# AccessPanelV1.net
KiCad netlist of a schematic drawn in EAGLE
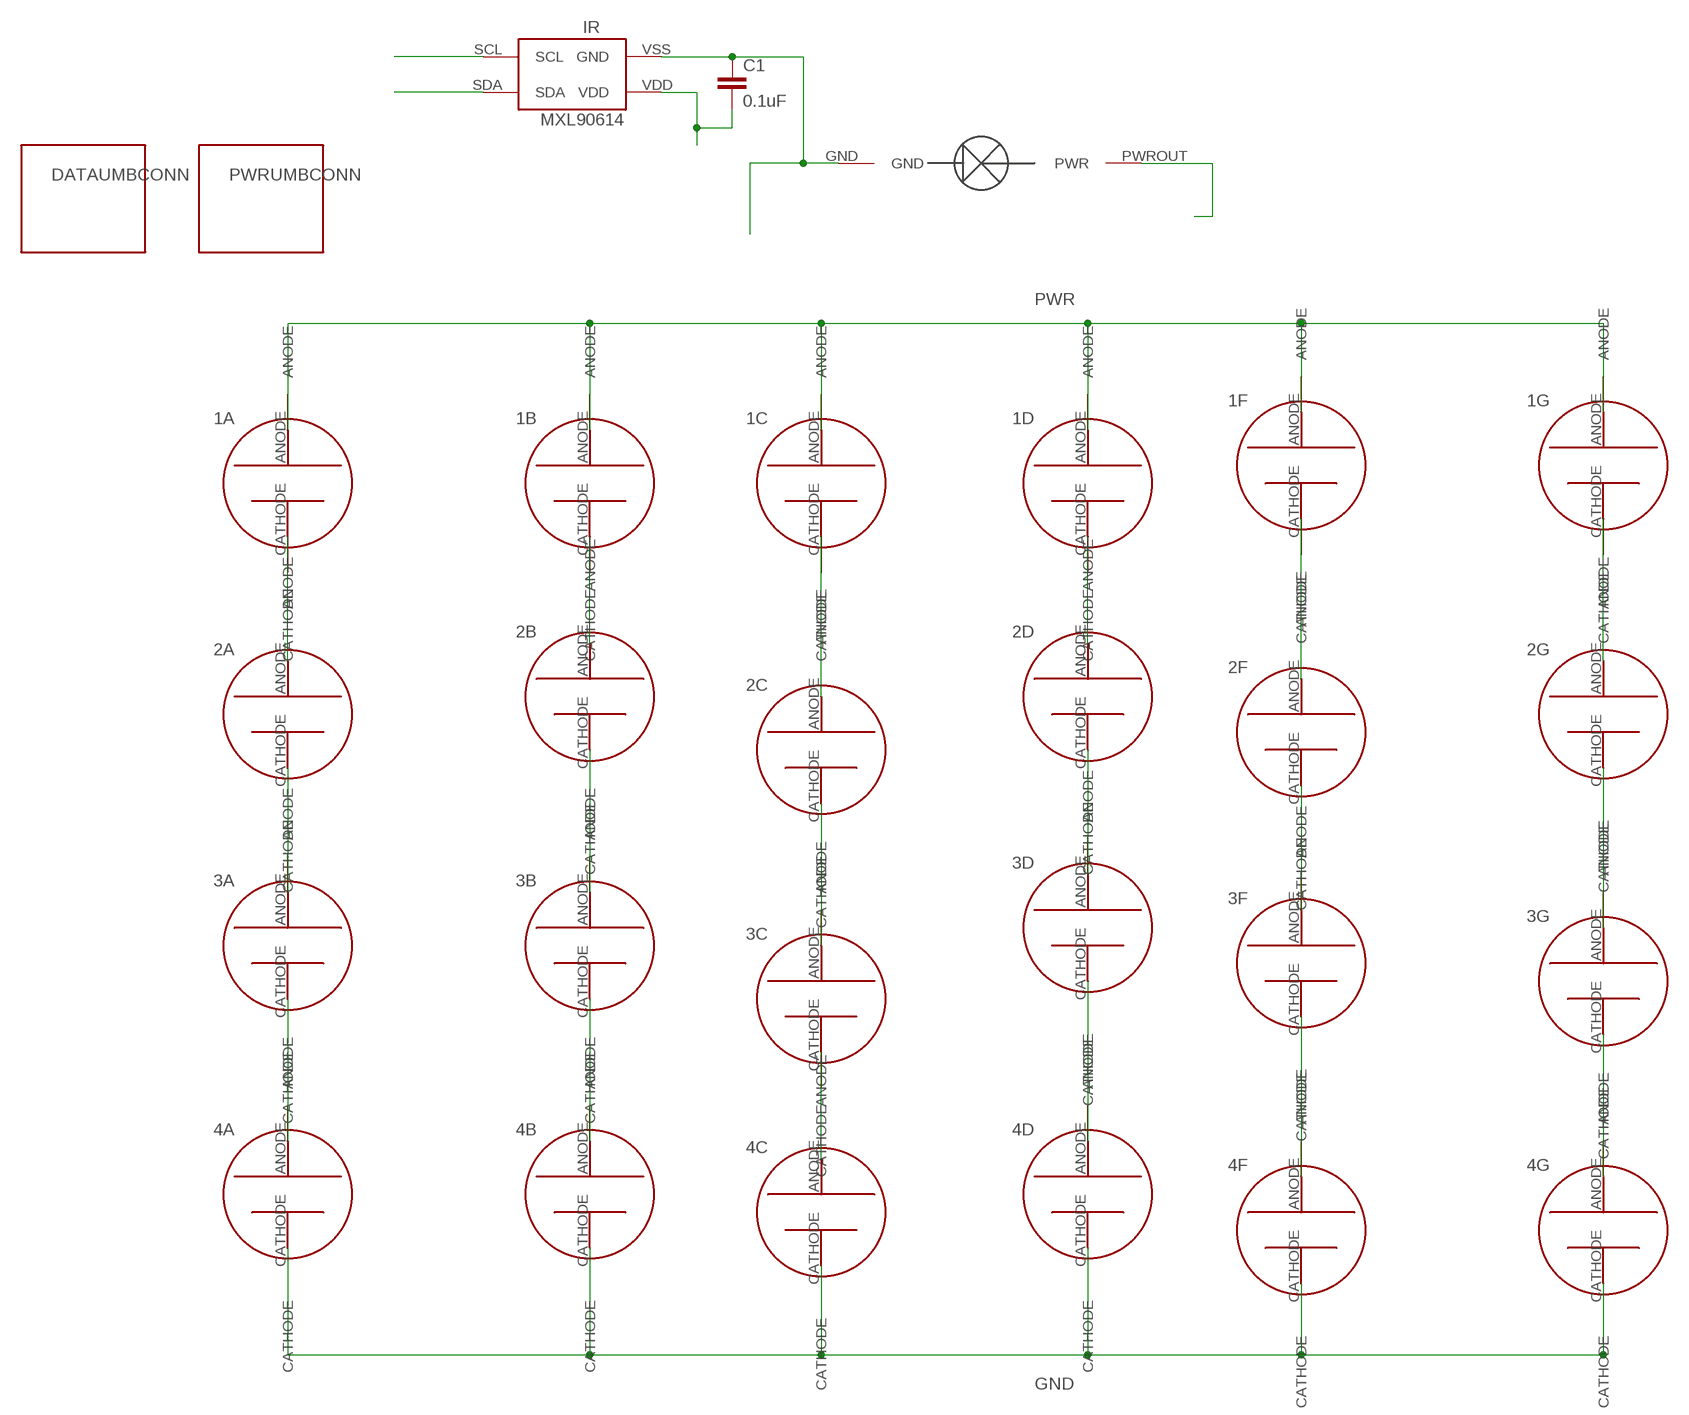
[diagram p0: schematic, sheet 1]

(export (version "E")
  (design (tool "Eeschema 10.0.6"))
  (components
    (comp (ref "1A")
      (value "NEWSOLARPANEL")
      (footprint "eagle-import:SOLARCELL2")
      (libsource (lib "eagle-import") (part "NEWSOLARPANEL"))
    )
    (comp (ref "1B")
      (value "NEWSOLARPANEL")
      (footprint "eagle-import:SOLARCELL2")
      (libsource (lib "eagle-import") (part "NEWSOLARPANEL"))
    )
    (comp (ref "1C")
      (value "NEWSOLARPANEL")
      (footprint "eagle-import:SOLARCELL2")
      (libsource (lib "eagle-import") (part "NEWSOLARPANEL"))
    )
    (comp (ref "1D")
      (value "NEWSOLARPANEL")
      (footprint "eagle-import:SOLARCELL2")
      (libsource (lib "eagle-import") (part "NEWSOLARPANEL"))
    )
    (comp (ref "1F")
      (value "NEWSOLARPANEL")
      (footprint "eagle-import:SOLARCELL2")
      (libsource (lib "eagle-import") (part "NEWSOLARPANEL"))
    )
    (comp (ref "1G")
      (value "NEWSOLARPANEL")
      (footprint "eagle-import:SOLARCELL2")
      (libsource (lib "eagle-import") (part "NEWSOLARPANEL"))
    )
    (comp (ref "2A")
      (value "NEWSOLARPANEL")
      (footprint "eagle-import:SOLARCELL2")
      (libsource (lib "eagle-import") (part "NEWSOLARPANEL"))
    )
    (comp (ref "2B")
      (value "NEWSOLARPANEL")
      (footprint "eagle-import:SOLARCELL2")
      (libsource (lib "eagle-import") (part "NEWSOLARPANEL"))
    )
    (comp (ref "2C")
      (value "NEWSOLARPANEL")
      (footprint "eagle-import:SOLARCELL2")
      (libsource (lib "eagle-import") (part "NEWSOLARPANEL"))
    )
    (comp (ref "2D")
      (value "NEWSOLARPANEL")
      (footprint "eagle-import:SOLARCELL2")
      (libsource (lib "eagle-import") (part "NEWSOLARPANEL"))
    )
    (comp (ref "2F")
      (value "NEWSOLARPANEL")
      (footprint "eagle-import:SOLARCELL2")
      (libsource (lib "eagle-import") (part "NEWSOLARPANEL"))
    )
    (comp (ref "2G")
      (value "NEWSOLARPANEL")
      (footprint "eagle-import:SOLARCELL2")
      (libsource (lib "eagle-import") (part "NEWSOLARPANEL"))
    )
    (comp (ref "3A")
      (value "NEWSOLARPANEL")
      (footprint "eagle-import:SOLARCELL2")
      (libsource (lib "eagle-import") (part "NEWSOLARPANEL"))
    )
    (comp (ref "3B")
      (value "NEWSOLARPANEL")
      (footprint "eagle-import:SOLARCELL2")
      (libsource (lib "eagle-import") (part "NEWSOLARPANEL"))
    )
    (comp (ref "3C")
      (value "NEWSOLARPANEL")
      (footprint "eagle-import:SOLARCELL2")
      (libsource (lib "eagle-import") (part "NEWSOLARPANEL"))
    )
    (comp (ref "3D")
      (value "NEWSOLARPANEL")
      (footprint "eagle-import:SOLARCELL2")
      (libsource (lib "eagle-import") (part "NEWSOLARPANEL"))
    )
    (comp (ref "3F")
      (value "NEWSOLARPANEL")
      (footprint "eagle-import:SOLARCELL2")
      (libsource (lib "eagle-import") (part "NEWSOLARPANEL"))
    )
    (comp (ref "3G")
      (value "NEWSOLARPANEL")
      (footprint "eagle-import:SOLARCELL2")
      (libsource (lib "eagle-import") (part "NEWSOLARPANEL"))
    )
    (comp (ref "4A")
      (value "NEWSOLARPANEL")
      (footprint "eagle-import:SOLARCELL2")
      (libsource (lib "eagle-import") (part "NEWSOLARPANEL"))
    )
    (comp (ref "4B")
      (value "NEWSOLARPANEL")
      (footprint "eagle-import:SOLARCELL2")
      (libsource (lib "eagle-import") (part "NEWSOLARPANEL"))
    )
    (comp (ref "4C")
      (value "NEWSOLARPANEL")
      (footprint "eagle-import:SOLARCELL2")
      (libsource (lib "eagle-import") (part "NEWSOLARPANEL"))
    )
    (comp (ref "4D")
      (value "NEWSOLARPANEL")
      (footprint "eagle-import:SOLARCELL2")
      (libsource (lib "eagle-import") (part "NEWSOLARPANEL"))
    )
    (comp (ref "4F")
      (value "NEWSOLARPANEL")
      (footprint "eagle-import:SOLARCELL2")
      (libsource (lib "eagle-import") (part "NEWSOLARPANEL"))
    )
    (comp (ref "4G")
      (value "NEWSOLARPANEL")
      (footprint "eagle-import:SOLARCELL2")
      (libsource (lib "eagle-import") (part "NEWSOLARPANEL"))
    )
    (comp (ref "C1")
      (value "0.1uF")
      (footprint "eagle-import:0805")
      (libsource (lib "eagle-import") (part "CAP0805"))
    )
    (comp (ref "DATAUMBCONN")
      (value "HARWIN_PWR_BOARDMOUNT")
      (footprint "eagle-import:HARWIN_PWR_BOARDMOUNT")
      (libsource (lib "eagle-import") (part "HARWIN_PWR_BOARDMOUNT"))
    )
    (comp (ref "IR")
      (value "MXL90620")
      (footprint "eagle-import:MXL90614")
      (libsource (lib "eagle-import") (part "MXL90620"))
    )
    (comp (ref "PHD")
      (value "PHOTODETECTOR")
      (footprint "eagle-import:PHOTODECTORDEVICE2")
      (libsource (lib "eagle-import") (part "PHOTODETECTOR"))
    )
    (comp (ref "PWRUMBCONN")
      (value "HARWIN_PWR_BOARDMOUNT")
      (footprint "eagle-import:HARWIN_PWR_BOARDMOUNT")
      (libsource (lib "eagle-import") (part "HARWIN_PWR_BOARDMOUNT"))
    )
  )
  (nets
    (net (code "1") (name "/GND") (class "Default")
      (node (ref "4A") (pin "CATHODE") (pinfunction "CATHODE_CATHODE") (pintype "bidirectional"))
      (node (ref "4B") (pin "CATHODE") (pinfunction "CATHODE_CATHODE") (pintype "bidirectional"))
      (node (ref "4C") (pin "CATHODE") (pinfunction "CATHODE_CATHODE") (pintype "bidirectional"))
      (node (ref "4D") (pin "CATHODE") (pinfunction "CATHODE_CATHODE") (pintype "bidirectional"))
      (node (ref "4F") (pin "CATHODE") (pinfunction "CATHODE_CATHODE") (pintype "bidirectional"))
      (node (ref "4G") (pin "CATHODE") (pinfunction "CATHODE_CATHODE") (pintype "bidirectional"))
      (node (ref "C1") (pin "1") (pinfunction "1_1") (pintype "passive"))
      (node (ref "IR") (pin "VSS") (pinfunction "GND_VSS") (pintype "bidirectional"))
      (node (ref "PHD") (pin "GND") (pinfunction "GND_GND") (pintype "bidirectional"))
    )
    (net (code "2") (name "/PWR") (class "Default")
      (node (ref "1A") (pin "ANODE") (pinfunction "ANODE_ANODE") (pintype "bidirectional"))
      (node (ref "1B") (pin "ANODE") (pinfunction "ANODE_ANODE") (pintype "bidirectional"))
      (node (ref "1C") (pin "ANODE") (pinfunction "ANODE_ANODE") (pintype "bidirectional"))
      (node (ref "1D") (pin "ANODE") (pinfunction "ANODE_ANODE") (pintype "bidirectional"))
      (node (ref "1F") (pin "ANODE") (pinfunction "ANODE_ANODE") (pintype "bidirectional"))
      (node (ref "1G") (pin "ANODE") (pinfunction "ANODE_ANODE") (pintype "bidirectional"))
    )
    (net (code "3") (name "Net-(1A-PadCATHODE)") (class "Default")
      (node (ref "1A") (pin "CATHODE") (pinfunction "CATHODE_CATHODE") (pintype "bidirectional"))
      (node (ref "2A") (pin "ANODE") (pinfunction "ANODE_ANODE") (pintype "bidirectional"))
    )
    (net (code "4") (name "Net-(1B-PadCATHODE)") (class "Default")
      (node (ref "1B") (pin "CATHODE") (pinfunction "CATHODE_CATHODE") (pintype "bidirectional"))
      (node (ref "2B") (pin "ANODE") (pinfunction "ANODE_ANODE") (pintype "bidirectional"))
    )
    (net (code "5") (name "Net-(1C-PadCATHODE)") (class "Default")
      (node (ref "1C") (pin "CATHODE") (pinfunction "CATHODE_CATHODE") (pintype "bidirectional"))
      (node (ref "2C") (pin "ANODE") (pinfunction "ANODE_ANODE") (pintype "bidirectional"))
    )
    (net (code "6") (name "Net-(1D-PadCATHODE)") (class "Default")
      (node (ref "1D") (pin "CATHODE") (pinfunction "CATHODE_CATHODE") (pintype "bidirectional"))
      (node (ref "2D") (pin "ANODE") (pinfunction "ANODE_ANODE") (pintype "bidirectional"))
    )
    (net (code "7") (name "Net-(1F-PadCATHODE)") (class "Default")
      (node (ref "1F") (pin "CATHODE") (pinfunction "CATHODE_CATHODE") (pintype "bidirectional"))
      (node (ref "2F") (pin "ANODE") (pinfunction "ANODE_ANODE") (pintype "bidirectional"))
    )
    (net (code "8") (name "Net-(1G-PadCATHODE)") (class "Default")
      (node (ref "1G") (pin "CATHODE") (pinfunction "CATHODE_CATHODE") (pintype "bidirectional"))
      (node (ref "2G") (pin "ANODE") (pinfunction "ANODE_ANODE") (pintype "bidirectional"))
    )
    (net (code "9") (name "Net-(2A-PadCATHODE)") (class "Default")
      (node (ref "2A") (pin "CATHODE") (pinfunction "CATHODE_CATHODE") (pintype "bidirectional"))
      (node (ref "3A") (pin "ANODE") (pinfunction "ANODE_ANODE") (pintype "bidirectional"))
    )
    (net (code "10") (name "Net-(2B-PadCATHODE)") (class "Default")
      (node (ref "2B") (pin "CATHODE") (pinfunction "CATHODE_CATHODE") (pintype "bidirectional"))
      (node (ref "3B") (pin "ANODE") (pinfunction "ANODE_ANODE") (pintype "bidirectional"))
    )
    (net (code "11") (name "Net-(2C-PadCATHODE)") (class "Default")
      (node (ref "2C") (pin "CATHODE") (pinfunction "CATHODE_CATHODE") (pintype "bidirectional"))
      (node (ref "3C") (pin "ANODE") (pinfunction "ANODE_ANODE") (pintype "bidirectional"))
    )
    (net (code "12") (name "Net-(2D-PadCATHODE)") (class "Default")
      (node (ref "2D") (pin "CATHODE") (pinfunction "CATHODE_CATHODE") (pintype "bidirectional"))
      (node (ref "3D") (pin "ANODE") (pinfunction "ANODE_ANODE") (pintype "bidirectional"))
    )
    (net (code "13") (name "Net-(2F-PadCATHODE)") (class "Default")
      (node (ref "2F") (pin "CATHODE") (pinfunction "CATHODE_CATHODE") (pintype "bidirectional"))
      (node (ref "3F") (pin "ANODE") (pinfunction "ANODE_ANODE") (pintype "bidirectional"))
    )
    (net (code "14") (name "Net-(2G-PadCATHODE)") (class "Default")
      (node (ref "2G") (pin "CATHODE") (pinfunction "CATHODE_CATHODE") (pintype "bidirectional"))
      (node (ref "3G") (pin "ANODE") (pinfunction "ANODE_ANODE") (pintype "bidirectional"))
    )
    (net (code "15") (name "Net-(3A-PadCATHODE)") (class "Default")
      (node (ref "3A") (pin "CATHODE") (pinfunction "CATHODE_CATHODE") (pintype "bidirectional"))
      (node (ref "4A") (pin "ANODE") (pinfunction "ANODE_ANODE") (pintype "bidirectional"))
    )
    (net (code "16") (name "Net-(3B-PadCATHODE)") (class "Default")
      (node (ref "3B") (pin "CATHODE") (pinfunction "CATHODE_CATHODE") (pintype "bidirectional"))
      (node (ref "4B") (pin "ANODE") (pinfunction "ANODE_ANODE") (pintype "bidirectional"))
    )
    (net (code "17") (name "Net-(3C-PadCATHODE)") (class "Default")
      (node (ref "3C") (pin "CATHODE") (pinfunction "CATHODE_CATHODE") (pintype "bidirectional"))
      (node (ref "4C") (pin "ANODE") (pinfunction "ANODE_ANODE") (pintype "bidirectional"))
    )
    (net (code "18") (name "Net-(3D-PadCATHODE)") (class "Default")
      (node (ref "3D") (pin "CATHODE") (pinfunction "CATHODE_CATHODE") (pintype "bidirectional"))
      (node (ref "4D") (pin "ANODE") (pinfunction "ANODE_ANODE") (pintype "bidirectional"))
    )
    (net (code "19") (name "Net-(3F-PadCATHODE)") (class "Default")
      (node (ref "3F") (pin "CATHODE") (pinfunction "CATHODE_CATHODE") (pintype "bidirectional"))
      (node (ref "4F") (pin "ANODE") (pinfunction "ANODE_ANODE") (pintype "bidirectional"))
    )
    (net (code "20") (name "Net-(3G-PadCATHODE)") (class "Default")
      (node (ref "3G") (pin "CATHODE") (pinfunction "CATHODE_CATHODE") (pintype "bidirectional"))
      (node (ref "4G") (pin "ANODE") (pinfunction "ANODE_ANODE") (pintype "bidirectional"))
    )
    (net (code "21") (name "Net-(C1-Pad2)") (class "Default")
      (node (ref "C1") (pin "2") (pinfunction "2_2") (pintype "passive"))
      (node (ref "IR") (pin "VDD") (pinfunction "VDD_VDD") (pintype "bidirectional"))
    )
    (net (code "22") (name "unconnected-(IR-PadSCL)") (class "Default")
      (node (ref "IR") (pin "SCL") (pinfunction "SCL_SCL") (pintype "bidirectional"))
    )
    (net (code "23") (name "unconnected-(IR-PadSDA)") (class "Default")
      (node (ref "IR") (pin "SDA") (pinfunction "SDA_SDA") (pintype "bidirectional"))
    )
    (net (code "24") (name "unconnected-(PHD-PWR-PadPWROUT)") (class "Default")
      (node (ref "PHD") (pin "PWROUT") (pinfunction "PWR_PWROUT") (pintype "bidirectional"))
    )
  )
)
